# Adafruit_Circuit_Playground_TFT_Gizmo.net
KiCad netlist of a schematic drawn in EAGLE
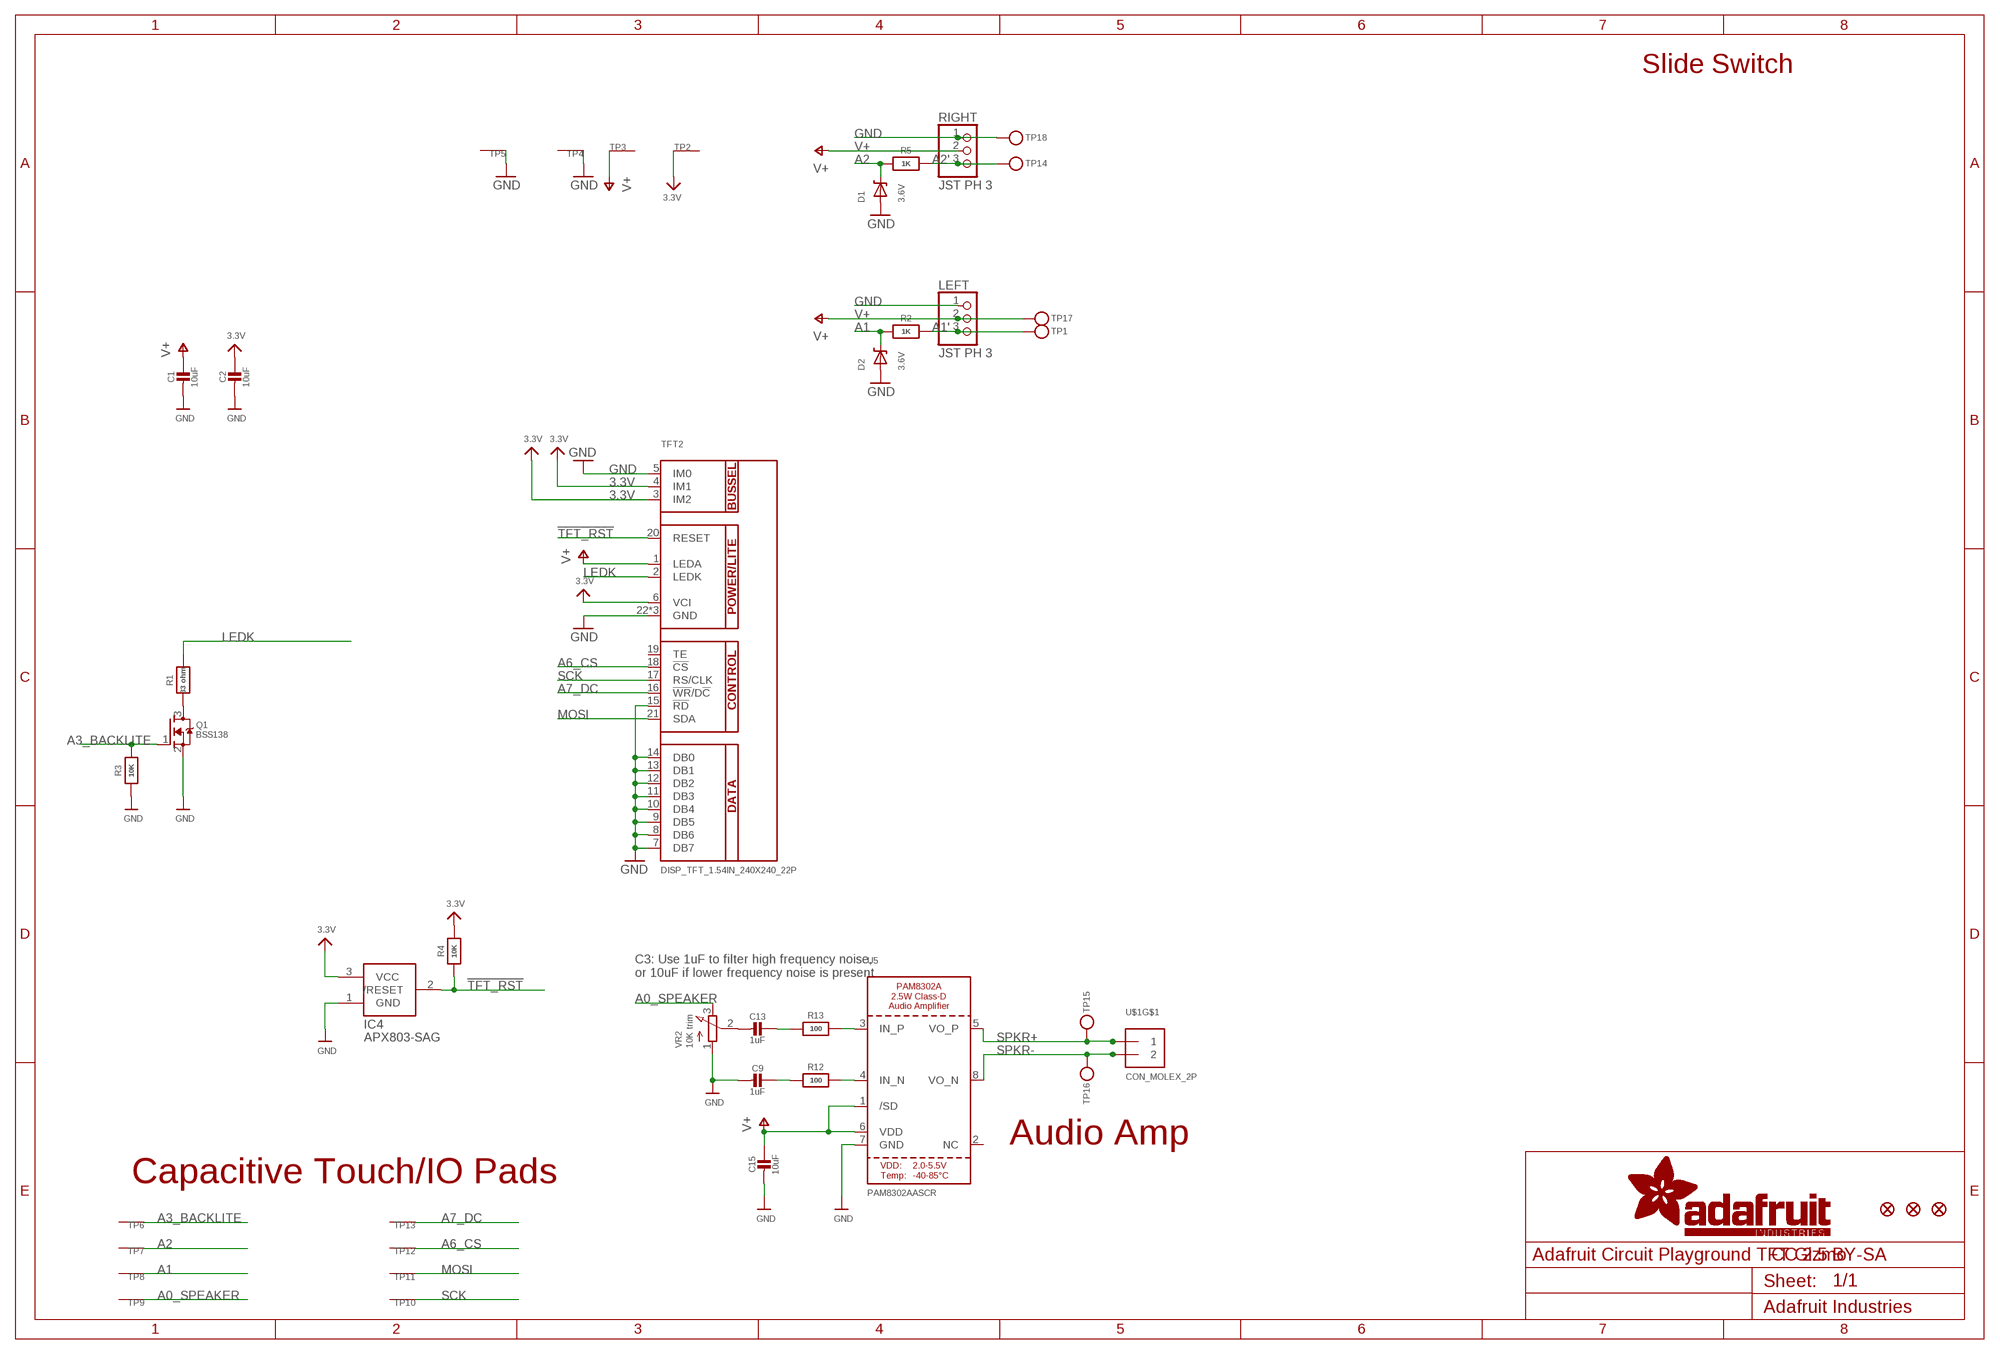
[diagram p0: schematic, sheet 1]

(export (version "E")
  (design (tool "Eeschema 10.0.6"))
  (components
    (comp (ref "C1")
      (value "10uF")
      (footprint "eagle-import:0805-NO")
      (libsource (lib "eagle-import") (part "CAP_CERAMIC0805-NOOUTLINE"))
    )
    (comp (ref "C2")
      (value "10uF")
      (footprint "eagle-import:0805-NO")
      (libsource (lib "eagle-import") (part "CAP_CERAMIC0805-NOOUTLINE"))
    )
    (comp (ref "C9")
      (value "1uF")
      (footprint "eagle-import:0603-NO")
      (libsource (lib "eagle-import") (part "CAP_CERAMIC0603_NO"))
    )
    (comp (ref "C13")
      (value "1uF")
      (footprint "eagle-import:0603-NO")
      (libsource (lib "eagle-import") (part "CAP_CERAMIC0603_NO"))
    )
    (comp (ref "C15")
      (value "10uF")
      (footprint "eagle-import:0805-NO")
      (libsource (lib "eagle-import") (part "CAP_CERAMIC0805-NOOUTLINE"))
    )
    (comp (ref "D1")
      (value "3.6V")
      (footprint "eagle-import:SOD-323")
      (libsource (lib "eagle-import") (part "DIODE-ZENERSOD323"))
    )
    (comp (ref "D2")
      (value "3.6V")
      (footprint "eagle-import:SOD-323")
      (libsource (lib "eagle-import") (part "DIODE-ZENERSOD323"))
    )
    (comp (ref "IC4")
      (value "APX803-SAG")
      (footprint "eagle-import:SOT23")
      (libsource (lib "eagle-import") (part "AXP083-SAG"))
    )
    (comp (ref "LEFT")
      (value "JST PH 3")
      (footprint "eagle-import:JSTPH3")
      (libsource (lib "eagle-import") (part "CON_JST_PH_3PIN"))
    )
    (comp (ref "Q1")
      (value "BSS138")
      (footprint "eagle-import:SOT23-WIDE")
      (libsource (lib "eagle-import") (part "MOSFET-NWIDE"))
    )
    (comp (ref "R1")
      (value "33 ohm")
      (footprint "eagle-import:0603-NO")
      (libsource (lib "eagle-import") (part "RESISTOR_0603_NOOUT"))
    )
    (comp (ref "R2")
      (value "1K")
      (footprint "eagle-import:0603-NO")
      (libsource (lib "eagle-import") (part "RESISTOR_0603_NOOUT"))
    )
    (comp (ref "R3")
      (value "10K")
      (footprint "eagle-import:0603-NO")
      (libsource (lib "eagle-import") (part "RESISTOR_0603_NOOUT"))
    )
    (comp (ref "R4")
      (value "10K")
      (footprint "eagle-import:0603-NO")
      (libsource (lib "eagle-import") (part "RESISTOR_0603_NOOUT"))
    )
    (comp (ref "R5")
      (value "1K")
      (footprint "eagle-import:0603-NO")
      (libsource (lib "eagle-import") (part "RESISTOR_0603_NOOUT"))
    )
    (comp (ref "R12")
      (value "100")
      (footprint "eagle-import:0603-NO")
      (libsource (lib "eagle-import") (part "RESISTOR_0603_NOOUT"))
    )
    (comp (ref "R13")
      (value "100")
      (footprint "eagle-import:0603-NO")
      (libsource (lib "eagle-import") (part "RESISTOR_0603_NOOUT"))
    )
    (comp (ref "RIGHT")
      (value "JST PH 3")
      (footprint "eagle-import:JSTPH3")
      (libsource (lib "eagle-import") (part "CON_JST_PH_3PIN"))
    )
    (comp (ref "TFT2")
      (value "DISP_TFT_1.54IN_240X240_22P")
      (footprint "eagle-import:TFT_1.54IN_240X240_22PIN")
      (libsource (lib "eagle-import") (part "DISP_TFT_1.54IN_240X240_22P"))
    )
    (comp (ref "TP1")
      (value "TESTPOINTROUND1.5MMNO")
      (footprint "eagle-import:TESTPOINT_ROUND_1.5MM_NO")
      (libsource (lib "eagle-import") (part "TESTPOINTROUND1.5MMNO"))
    )
    (comp (ref "TP2")
      (value "SEWTAP_SMTNUTM3")
      (footprint "eagle-import:SMT_NUT_3MM")
      (libsource (lib "eagle-import") (part "SEWTAP_SMTNUTM3"))
    )
    (comp (ref "TP3")
      (value "SEWTAP_SMTNUTM3")
      (footprint "eagle-import:SMT_NUT_3MM")
      (libsource (lib "eagle-import") (part "SEWTAP_SMTNUTM3"))
    )
    (comp (ref "TP4")
      (value "SEWTAP_SMTNUTM3")
      (footprint "eagle-import:SMT_NUT_3MM")
      (libsource (lib "eagle-import") (part "SEWTAP_SMTNUTM3"))
    )
    (comp (ref "TP5")
      (value "SEWTAP_SMTNUTM3")
      (footprint "eagle-import:SMT_NUT_3MM")
      (libsource (lib "eagle-import") (part "SEWTAP_SMTNUTM3"))
    )
    (comp (ref "TP6")
      (value "SEWTAP_SMTNUTM3")
      (footprint "eagle-import:SMT_NUT_3MM")
      (libsource (lib "eagle-import") (part "SEWTAP_SMTNUTM3"))
    )
    (comp (ref "TP7")
      (value "SEWTAP_SMTNUTM3")
      (footprint "eagle-import:SMT_NUT_3MM")
      (libsource (lib "eagle-import") (part "SEWTAP_SMTNUTM3"))
    )
    (comp (ref "TP8")
      (value "SEWTAP_SMTNUTM3")
      (footprint "eagle-import:SMT_NUT_3MM")
      (libsource (lib "eagle-import") (part "SEWTAP_SMTNUTM3"))
    )
    (comp (ref "TP9")
      (value "SEWTAP_SMTNUTM3")
      (footprint "eagle-import:SMT_NUT_3MM")
      (libsource (lib "eagle-import") (part "SEWTAP_SMTNUTM3"))
    )
    (comp (ref "TP10")
      (value "SEWTAP_SMTNUTM3")
      (footprint "eagle-import:SMT_NUT_3MM")
      (libsource (lib "eagle-import") (part "SEWTAP_SMTNUTM3"))
    )
    (comp (ref "TP11")
      (value "SEWTAP_SMTNUTM3")
      (footprint "eagle-import:SMT_NUT_3MM")
      (libsource (lib "eagle-import") (part "SEWTAP_SMTNUTM3"))
    )
    (comp (ref "TP12")
      (value "SEWTAP_SMTNUTM3")
      (footprint "eagle-import:SMT_NUT_3MM")
      (libsource (lib "eagle-import") (part "SEWTAP_SMTNUTM3"))
    )
    (comp (ref "TP13")
      (value "SEWTAP_SMTNUTM3")
      (footprint "eagle-import:SMT_NUT_3MM")
      (libsource (lib "eagle-import") (part "SEWTAP_SMTNUTM3"))
    )
    (comp (ref "TP14")
      (value "TESTPOINTROUND1.5MMNO")
      (footprint "eagle-import:TESTPOINT_ROUND_1.5MM_NO")
      (libsource (lib "eagle-import") (part "TESTPOINTROUND1.5MMNO"))
    )
    (comp (ref "TP15")
      (value "TESTPOINTROUND1.5MMNO")
      (footprint "eagle-import:TESTPOINT_ROUND_1.5MM_NO")
      (libsource (lib "eagle-import") (part "TESTPOINTROUND1.5MMNO"))
    )
    (comp (ref "TP16")
      (value "TESTPOINTROUND1.5MMNO")
      (footprint "eagle-import:TESTPOINT_ROUND_1.5MM_NO")
      (libsource (lib "eagle-import") (part "TESTPOINTROUND1.5MMNO"))
    )
    (comp (ref "TP17")
      (value "TESTPOINTROUND1.5MMNO")
      (footprint "eagle-import:TESTPOINT_ROUND_1.5MM_NO")
      (libsource (lib "eagle-import") (part "TESTPOINTROUND1.5MMNO"))
    )
    (comp (ref "TP18")
      (value "TESTPOINTROUND1.5MMNO")
      (footprint "eagle-import:TESTPOINT_ROUND_1.5MM_NO")
      (libsource (lib "eagle-import") (part "TESTPOINTROUND1.5MMNO"))
    )
    (comp (ref "U$1")
      (value "CON_MOLEX_2P")
      (footprint "eagle-import:53398-0271")
      (libsource (lib "eagle-import") (part "CON_MOLEX_2P"))
    )
    (comp (ref "U$2")
      (value "FIDUCIAL_1MM")
      (footprint "eagle-import:FIDUCIAL_1MM")
      (libsource (lib "eagle-import") (part "FIDUCIAL_1MM"))
    )
    (comp (ref "U$3")
      (value "FIDUCIAL_1MM")
      (footprint "eagle-import:FIDUCIAL_1MM")
      (fields (field (name "BOM") "EXCLUDE"))
      (libsource (lib "eagle-import") (part "FIDUCIAL_1MM"))
    )
    (comp (ref "U$6")
      (value "FIDUCIAL_1MM")
      (footprint "eagle-import:FIDUCIAL_1MM")
      (libsource (lib "eagle-import") (part "FIDUCIAL_1MM"))
    )
    (comp (ref "U5")
      (value "PAM8302AASCR")
      (footprint "eagle-import:MSOP8_0.65MM")
      (libsource (lib "eagle-import") (part "AUDIOAMP_PAM8302A"))
    )
    (comp (ref "VR2")
      (value "10K trim")
      (footprint "eagle-import:TRIMPOT_BOURNS_3303W")
      (libsource (lib "eagle-import") (part "TRIMPOT3303W/X"))
    )
  )
  (nets
    (net (code "1") (name "/A0_SPEAKER") (class "Default")
      (node (ref "TP9") (pin "P$1") (pinfunction "SEW_P$1") (pintype "bidirectional"))
      (node (ref "VR2") (pin "3") (pinfunction "E_3") (pintype "passive"))
    )
    (net (code "2") (name "/A1") (class "Default")
      (node (ref "D2") (pin "C") (pinfunction "C_C") (pintype "passive"))
      (node (ref "R2") (pin "2") (pinfunction "2_2") (pintype "passive"))
      (node (ref "TP8") (pin "P$1") (pinfunction "SEW_P$1") (pintype "bidirectional"))
    )
    (net (code "3") (name "/A1'") (class "Default")
      (node (ref "LEFT") (pin "3") (pinfunction "3_3") (pintype "passive"))
      (node (ref "R2") (pin "1") (pinfunction "1_1") (pintype "passive"))
      (node (ref "TP1") (pin "P$1") (pinfunction "P$1_P$1") (pintype "bidirectional"))
    )
    (net (code "4") (name "/A2") (class "Default")
      (node (ref "D1") (pin "C") (pinfunction "C_C") (pintype "passive"))
      (node (ref "R5") (pin "2") (pinfunction "2_2") (pintype "passive"))
      (node (ref "TP7") (pin "P$1") (pinfunction "SEW_P$1") (pintype "bidirectional"))
    )
    (net (code "5") (name "/A2'") (class "Default")
      (node (ref "R5") (pin "1") (pinfunction "1_1") (pintype "passive"))
      (node (ref "RIGHT") (pin "3") (pinfunction "3_3") (pintype "passive"))
      (node (ref "TP14") (pin "P$1") (pinfunction "P$1_P$1") (pintype "bidirectional"))
    )
    (net (code "6") (name "/A3_BACKLITE") (class "Default")
      (node (ref "Q1") (pin "1") (pinfunction "G_1") (pintype "bidirectional"))
      (node (ref "R3") (pin "2") (pinfunction "2_2") (pintype "passive"))
      (node (ref "TP6") (pin "P$1") (pinfunction "SEW_P$1") (pintype "bidirectional"))
    )
    (net (code "7") (name "/A6_CS") (class "Default")
      (node (ref "TFT2") (pin "18") (pinfunction "~{CS}_18") (pintype "input"))
      (node (ref "TP12") (pin "P$1") (pinfunction "SEW_P$1") (pintype "bidirectional"))
    )
    (net (code "8") (name "/A7_DC") (class "Default")
      (node (ref "TFT2") (pin "16") (pinfunction "~{WR}/D~{C}_16") (pintype "input"))
      (node (ref "TP13") (pin "P$1") (pinfunction "SEW_P$1") (pintype "bidirectional"))
    )
    (net (code "9") (name "/LEDK") (class "Default")
      (node (ref "R1") (pin "2") (pinfunction "2_2") (pintype "passive"))
      (node (ref "TFT2") (pin "2") (pinfunction "LEDK_2") (pintype "input"))
    )
    (net (code "10") (name "/MOSI") (class "Default")
      (node (ref "TFT2") (pin "21") (pinfunction "SDA_21") (pintype "bidirectional"))
      (node (ref "TP11") (pin "P$1") (pinfunction "SEW_P$1") (pintype "bidirectional"))
    )
    (net (code "11") (name "/SCK") (class "Default")
      (node (ref "TFT2") (pin "17") (pinfunction "RS/CLK_17") (pintype "input"))
      (node (ref "TP10") (pin "P$1") (pinfunction "SEW_P$1") (pintype "bidirectional"))
    )
    (net (code "12") (name "/SPKR+") (class "Default")
      (node (ref "TP15") (pin "P$1") (pinfunction "P$1_P$1") (pintype "bidirectional"))
      (node (ref "U$1") (pin "1") (pinfunction "1_1") (pintype "passive"))
      (node (ref "U5") (pin "5") (pinfunction "VO_P_5") (pintype "output"))
    )
    (net (code "13") (name "/SPKR-") (class "Default")
      (node (ref "TP16") (pin "P$1") (pinfunction "P$1_P$1") (pintype "bidirectional"))
      (node (ref "U$1") (pin "2") (pinfunction "2_2") (pintype "passive"))
      (node (ref "U5") (pin "8") (pinfunction "VO_N_8") (pintype "output"))
    )
    (net (code "14") (name "/~{TFT_RST}") (class "Default")
      (node (ref "IC4") (pin "2") (pinfunction "/RESET_2") (pintype "output"))
      (node (ref "R4") (pin "1") (pinfunction "1_1") (pintype "passive"))
      (node (ref "TFT2") (pin "20") (pinfunction "RESET_20") (pintype "input"))
    )
    (net (code "15") (name "3.3V") (class "Default")
      (node (ref "C2") (pin "1") (pinfunction "1_1") (pintype "passive"))
      (node (ref "IC4") (pin "3") (pinfunction "VCC_3") (pintype "power_in"))
      (node (ref "R4") (pin "2") (pinfunction "2_2") (pintype "passive"))
      (node (ref "TFT2") (pin "3") (pinfunction "IM2_3") (pintype "input"))
      (node (ref "TFT2") (pin "4") (pinfunction "IM1_4") (pintype "input"))
      (node (ref "TFT2") (pin "6") (pinfunction "VCI_6") (pintype "power_in"))
      (node (ref "TP2") (pin "P$1") (pinfunction "SEW_P$1") (pintype "bidirectional"))
    )
    (net (code "16") (name "GND") (class "Default")
      (node (ref "C1") (pin "2") (pinfunction "2_2") (pintype "passive"))
      (node (ref "C15") (pin "2") (pinfunction "2_2") (pintype "passive"))
      (node (ref "C2") (pin "2") (pinfunction "2_2") (pintype "passive"))
      (node (ref "C9") (pin "2") (pinfunction "2_2") (pintype "passive"))
      (node (ref "D1") (pin "A") (pinfunction "A_A") (pintype "passive"))
      (node (ref "D2") (pin "A") (pinfunction "A_A") (pintype "passive"))
      (node (ref "IC4") (pin "1") (pinfunction "GND_1") (pintype "power_in"))
      (node (ref "LEFT") (pin "1") (pinfunction "1_1") (pintype "passive"))
      (node (ref "Q1") (pin "2") (pinfunction "S_2") (pintype "bidirectional"))
      (node (ref "R3") (pin "1") (pinfunction "1_1") (pintype "passive"))
      (node (ref "RIGHT") (pin "1") (pinfunction "1_1") (pintype "passive"))
      (node (ref "TFT2") (pin "10") (pinfunction "DB4_10") (pintype "bidirectional"))
      (node (ref "TFT2") (pin "11") (pinfunction "DB3_11") (pintype "bidirectional"))
      (node (ref "TFT2") (pin "12") (pinfunction "DB2_12") (pintype "bidirectional"))
      (node (ref "TFT2") (pin "13") (pinfunction "DB1_13") (pintype "bidirectional"))
      (node (ref "TFT2") (pin "14") (pinfunction "DB0_14") (pintype "bidirectional"))
      (node (ref "TFT2") (pin "15") (pinfunction "~{RD}_15") (pintype "input"))
      (node (ref "TFT2") (pin "22") (pinfunction "GND_22") (pintype "power_in"))
      (node (ref "TFT2") (pin "5") (pinfunction "IM0_5") (pintype "input"))
      (node (ref "TFT2") (pin "7") (pinfunction "DB7_7") (pintype "bidirectional"))
      (node (ref "TFT2") (pin "8") (pinfunction "DB6_8") (pintype "bidirectional"))
      (node (ref "TFT2") (pin "9") (pinfunction "DB5_9") (pintype "bidirectional"))
      (node (ref "TFT2") (pin "SUPPORT1") (pinfunction "GND_SUPPORT1") (pintype "power_in"))
      (node (ref "TFT2") (pin "SUPPORT2") (pinfunction "GND_SUPPORT2") (pintype "power_in"))
      (node (ref "TP18") (pin "P$1") (pinfunction "P$1_P$1") (pintype "bidirectional"))
      (node (ref "TP4") (pin "P$1") (pinfunction "SEW_P$1") (pintype "bidirectional"))
      (node (ref "TP5") (pin "P$1") (pinfunction "SEW_P$1") (pintype "bidirectional"))
      (node (ref "U5") (pin "7") (pinfunction "GND_7") (pintype "power_in"))
      (node (ref "VR2") (pin "1") (pinfunction "A_1") (pintype "passive"))
    )
    (net (code "17") (name "Net-(C9-Pad1)") (class "Default")
      (node (ref "C9") (pin "1") (pinfunction "1_1") (pintype "passive"))
      (node (ref "R12") (pin "1") (pinfunction "1_1") (pintype "passive"))
    )
    (net (code "18") (name "Net-(C13-Pad1)") (class "Default")
      (node (ref "C13") (pin "1") (pinfunction "1_1") (pintype "passive"))
      (node (ref "R13") (pin "1") (pinfunction "1_1") (pintype "passive"))
    )
    (net (code "19") (name "Net-(Q1-D)") (class "Default")
      (node (ref "Q1") (pin "3") (pinfunction "D_3") (pintype "bidirectional"))
      (node (ref "R1") (pin "1") (pinfunction "1_1") (pintype "passive"))
    )
    (net (code "20") (name "Net-(U5-IN_N)") (class "Default")
      (node (ref "R12") (pin "2") (pinfunction "2_2") (pintype "passive"))
      (node (ref "U5") (pin "4") (pinfunction "IN_N_4") (pintype "input"))
    )
    (net (code "21") (name "Net-(U5-IN_P)") (class "Default")
      (node (ref "R13") (pin "2") (pinfunction "2_2") (pintype "passive"))
      (node (ref "U5") (pin "3") (pinfunction "IN_P_3") (pintype "input"))
    )
    (net (code "22") (name "Net-(VR2-S)") (class "Default")
      (node (ref "C13") (pin "2") (pinfunction "2_2") (pintype "passive"))
      (node (ref "VR2") (pin "2") (pinfunction "S_2") (pintype "passive"))
    )
    (net (code "23") (name "V+") (class "Default")
      (node (ref "C1") (pin "1") (pinfunction "1_1") (pintype "passive"))
      (node (ref "C15") (pin "1") (pinfunction "1_1") (pintype "passive"))
      (node (ref "LEFT") (pin "2") (pinfunction "2_2") (pintype "passive"))
      (node (ref "RIGHT") (pin "2") (pinfunction "2_2") (pintype "passive"))
      (node (ref "TFT2") (pin "1") (pinfunction "LEDA_1") (pintype "input"))
      (node (ref "TP17") (pin "P$1") (pinfunction "P$1_P$1") (pintype "bidirectional"))
      (node (ref "TP3") (pin "P$1") (pinfunction "SEW_P$1") (pintype "bidirectional"))
      (node (ref "U5") (pin "1") (pinfunction "/SD_1") (pintype "input"))
      (node (ref "U5") (pin "6") (pinfunction "VDD_6") (pintype "power_in"))
    )
    (net (code "24") (name "unconnected-(TFT2-TE-Pad19)") (class "Default")
      (node (ref "TFT2") (pin "19") (pinfunction "TE_19") (pintype "output"))
    )
    (net (code "25") (name "unconnected-(U5-NC-Pad2)") (class "Default")
      (node (ref "U5") (pin "2") (pinfunction "NC_2") (pintype "no_connect"))
    )
  )
)
